# 1-Schematic.net
KiCad netlist of a schematic drawn in EasyEDA
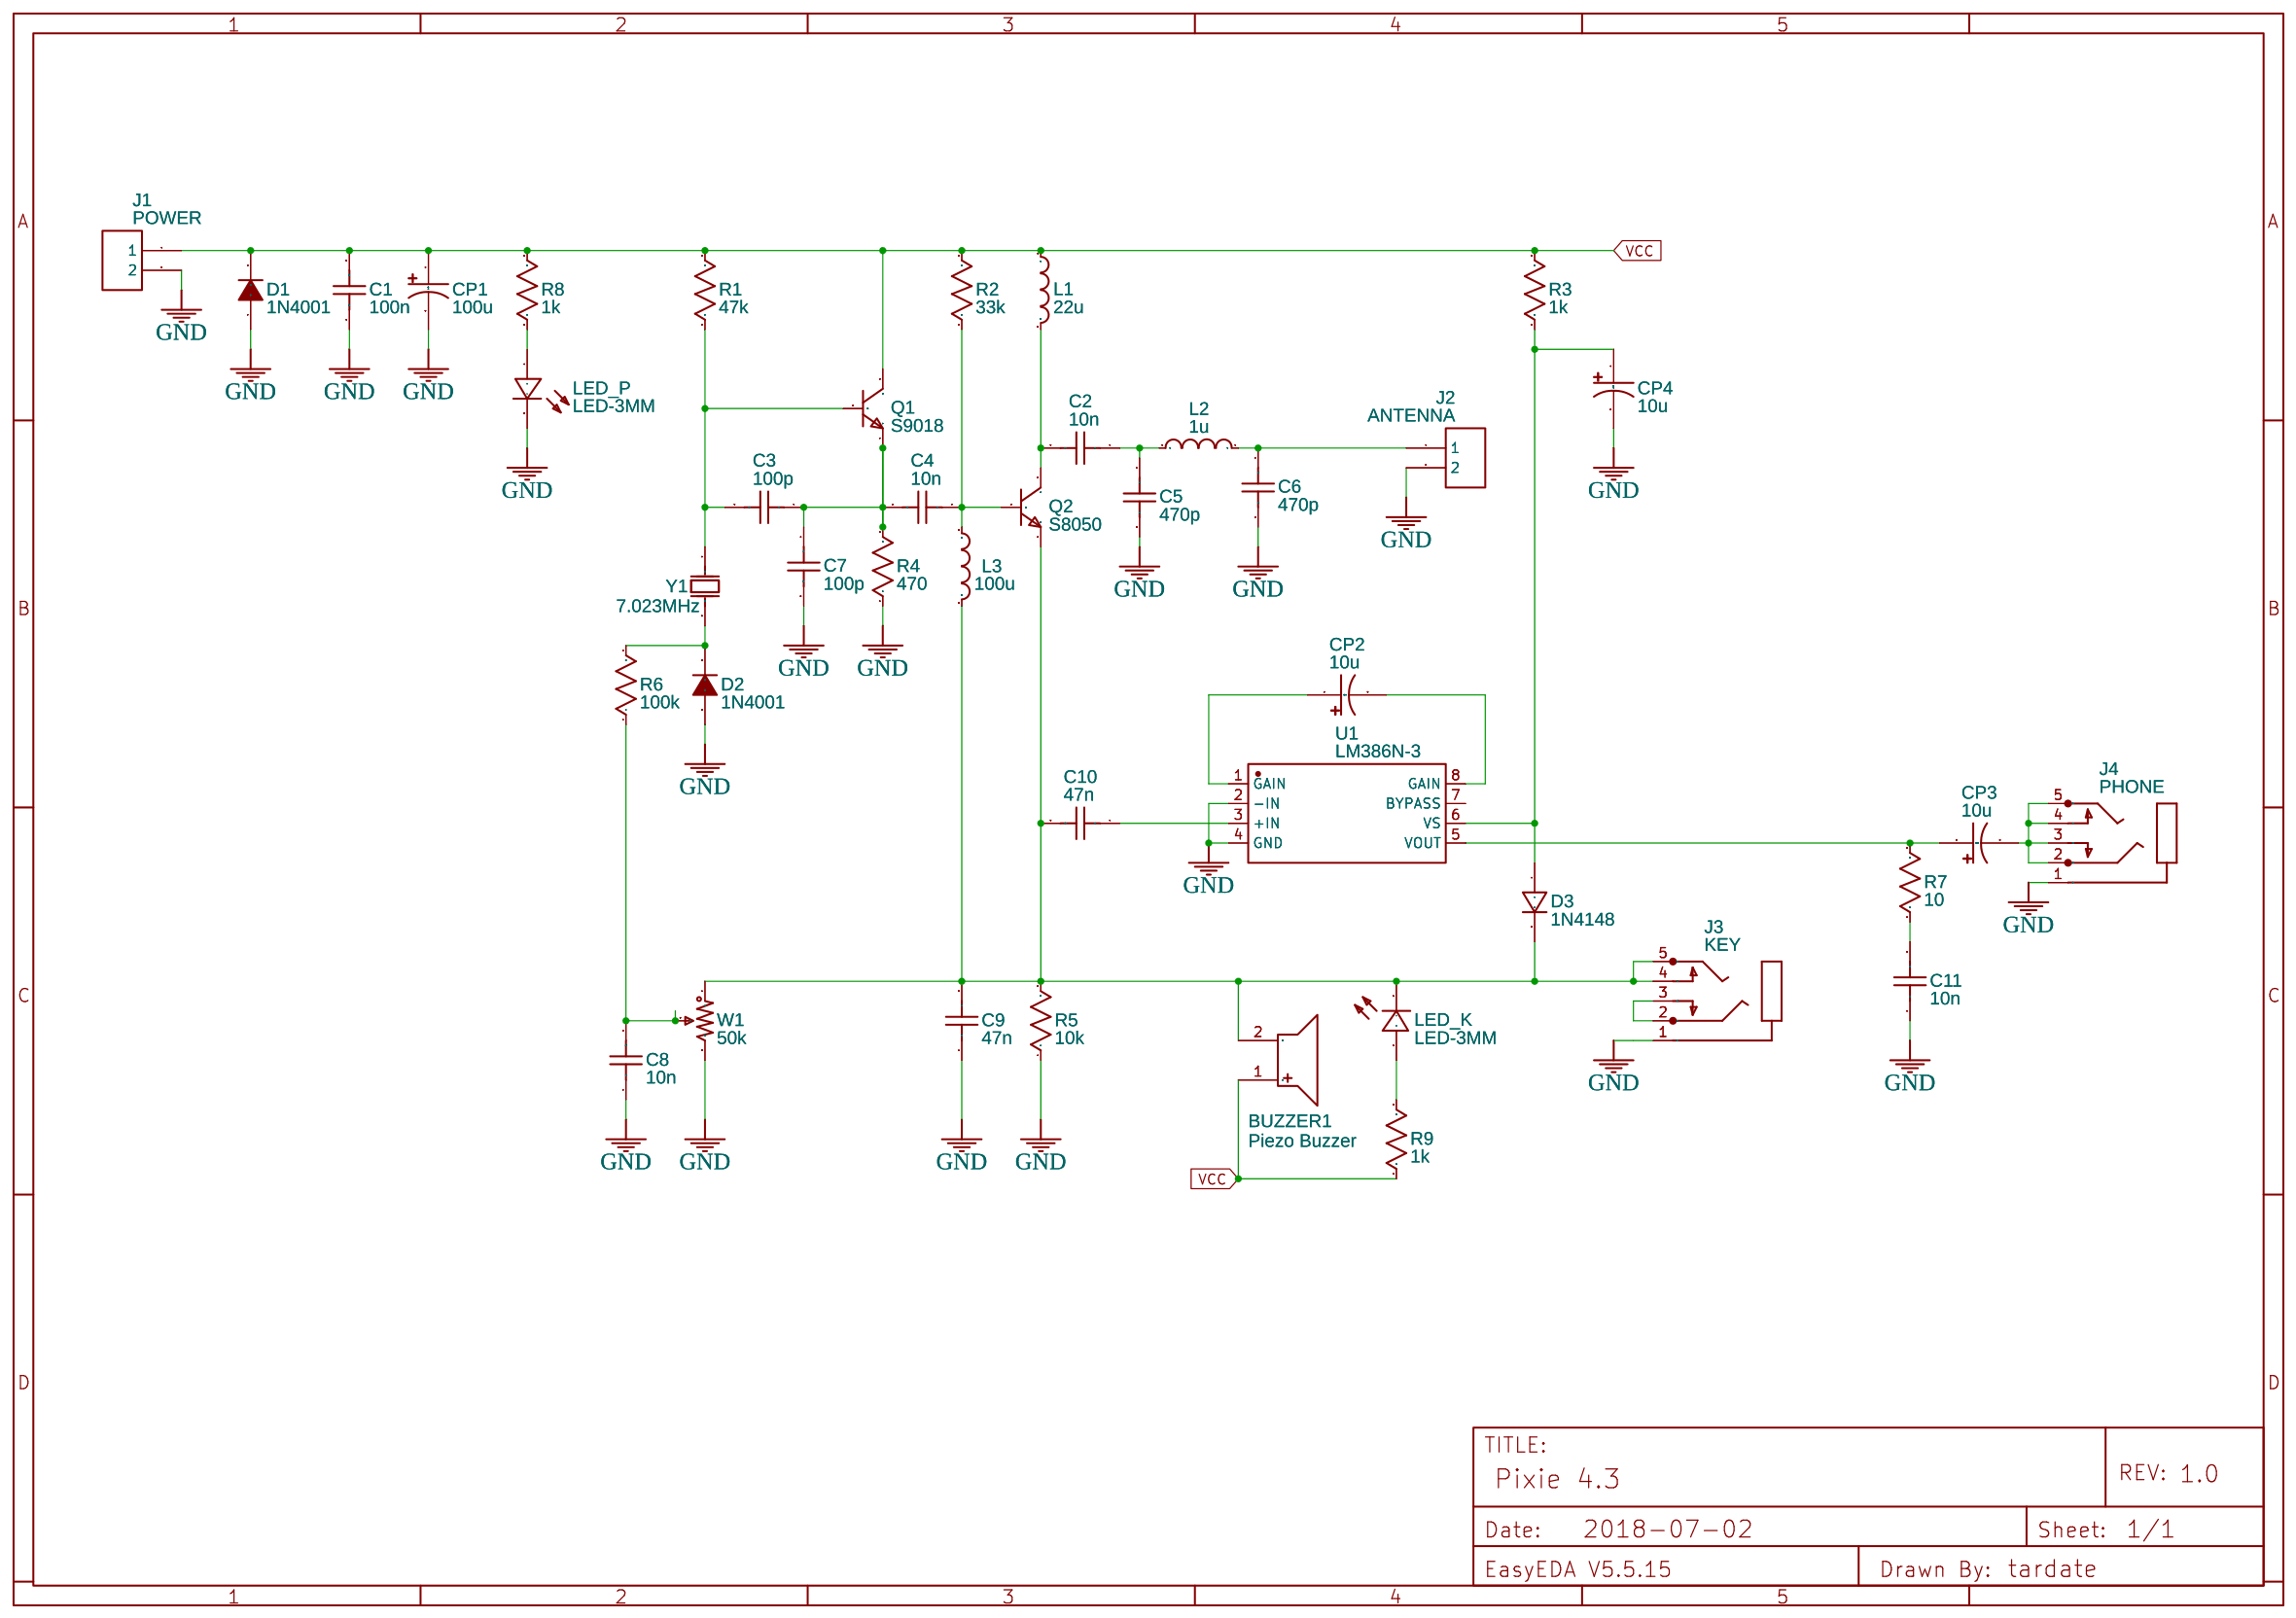
[diagram p0: schematic sheet]

(export (version "E")
  (design (tool "Eeschema 10.0.6"))
  (components
    (comp (ref "BUZZER1")
      (value "Piezo Buzzer")
      (fields (field (name "BOM_Manufacturer Part") "buzzerHMB1275-12B"))
      (libsource (lib "") (part "Unknown_640_530"))
    )
    (comp (ref "C1")
      (value "100n")
      (fields (field (name "BOM_Manufacturer Part") "?"))
      (libsource (lib "") (part "Cap_RAD-0.1_US"))
    )
    (comp (ref "C2")
      (value "10n")
      (fields (field (name "BOM_Manufacturer Part") "?"))
      (libsource (lib "") (part "Cap_RAD-0.1_US_2"))
    )
    (comp (ref "C3")
      (value "100p")
      (fields (field (name "BOM_Manufacturer Part") "?"))
      (libsource (lib "") (part "Cap_RAD-0.1_US_2"))
    )
    (comp (ref "C4")
      (value "10n")
      (fields (field (name "BOM_Manufacturer Part") "?"))
      (libsource (lib "") (part "Cap_RAD-0.1_US_2"))
    )
    (comp (ref "C5")
      (value "470p")
      (fields (field (name "BOM_Manufacturer Part") "?"))
      (libsource (lib "") (part "Cap_RAD-0.1_US_1"))
    )
    (comp (ref "C6")
      (value "470p")
      (fields (field (name "BOM_Manufacturer Part") "?"))
      (libsource (lib "") (part "Cap_RAD-0.1_US_1"))
    )
    (comp (ref "C7")
      (value "100p")
      (fields (field (name "BOM_Manufacturer Part") "?"))
      (libsource (lib "") (part "Cap_RAD-0.1_US_1"))
    )
    (comp (ref "C8")
      (value "10n")
      (fields (field (name "BOM_Manufacturer Part") "?"))
      (libsource (lib "") (part "Cap_RAD-0.1_US"))
    )
    (comp (ref "C9")
      (value "47n")
      (fields (field (name "BOM_Manufacturer Part") "?"))
      (libsource (lib "") (part "Cap_RAD-0.1_US"))
    )
    (comp (ref "C10")
      (value "47n")
      (fields (field (name "BOM_Manufacturer Part") "?"))
      (libsource (lib "") (part "Cap_RAD-0.1_US_2"))
    )
    (comp (ref "C11")
      (value "10n")
      (fields (field (name "BOM_Manufacturer Part") "?"))
      (libsource (lib "") (part "Cap_RAD-0.1_US"))
    )
    (comp (ref "CP1")
      (value "100u")
      (fields (field (name "BOM_Manufacturer Part") "?"))
      (libsource (lib "") (part "Cap_Electrolytic(TH)_D3.0XF1.5_US_2"))
    )
    (comp (ref "CP2")
      (value "10u")
      (fields (field (name "BOM_Manufacturer Part") "?"))
      (libsource (lib "") (part "Cap_Electrolytic(TH)_D3.0XF1.5_US"))
    )
    (comp (ref "CP3")
      (value "10u")
      (fields (field (name "BOM_Manufacturer Part") "?"))
      (libsource (lib "") (part "Cap_Electrolytic(TH)_D3.0XF1.5_US"))
    )
    (comp (ref "CP4")
      (value "10u")
      (fields (field (name "BOM_Manufacturer Part") "?"))
      (libsource (lib "") (part "Cap_Electrolytic(TH)_D3.0XF1.5_US_1"))
    )
    (comp (ref "D1")
      (value "1N4001")
      (fields (field (name "BOM_Manufacturer Part") "1N4001-E3/73"))
      (libsource (lib "") (part "Unknown_120_140"))
    )
    (comp (ref "D2")
      (value "1N4001")
      (fields (field (name "BOM_Manufacturer Part") "1N4001-E3/73"))
      (libsource (lib "") (part "Unknown_350_340"))
    )
    (comp (ref "D3")
      (value "1N4148")
      (fields (field (name "BOM_Manufacturer Part") "1N4448"))
      (libsource (lib "") (part "Unknown_770_450"))
    )
    (comp (ref "J1")
      (value "POWER")
      (fields (field (name "BOM_Manufacturer Part") "?"))
      (libsource (lib "") (part "Unknown_45_110"))
    )
    (comp (ref "J2")
      (value "ANTENNA")
      (fields (field (name "BOM_Manufacturer Part") "?"))
      (libsource (lib "") (part "Unknown_745_210"))
    )
    (comp (ref "J3")
      (value "KEY")
      (fields (field (name "BOM_Manufacturer Part") "?"))
      (libsource (lib "") (part "Unknown_880_490"))
    )
    (comp (ref "J4")
      (value "PHONE")
      (fields (field (name "BOM_Manufacturer Part") "?"))
      (libsource (lib "") (part "Unknown_1080_410"))
    )
    (comp (ref "L1")
      (value "22u")
      (fields (field (name "BOM_Manufacturer Part") "?"))
      (libsource (lib "") (part "Inductor_AXIAL-0.4_US_2"))
    )
    (comp (ref "L2")
      (value "1u")
      (fields (field (name "BOM_Manufacturer Part") "?"))
      (libsource (lib "") (part "Inductor_AXIAL-0.4_US_1"))
    )
    (comp (ref "L3")
      (value "100u")
      (fields (field (name "BOM_Manufacturer Part") "?"))
      (libsource (lib "") (part "Inductor_AXIAL-0.4_US"))
    )
    (comp (ref "LED_K")
      (value "LED-3MM")
      (fields (field (name "BOM_Manufacturer Part") "204-10SURD/S530-A3"))
      (libsource (lib "") (part "Unknown_700_510"))
    )
    (comp (ref "LED_P")
      (value "LED-3MM")
      (fields (field (name "BOM_Manufacturer Part") "204-10SURD/S530-A3"))
      (libsource (lib "") (part "Unknown_260_190"))
    )
    (comp (ref "Q1")
      (value "S9018")
      (fields (field (name "BOM_Manufacturer Part") "2N3904"))
      (libsource (lib "") (part "Unknown_430_200"))
    )
    (comp (ref "Q2")
      (value "S8050")
      (fields (field (name "BOM_Manufacturer Part") "2N3904"))
      (libsource (lib "") (part "Unknown_510_250"))
    )
    (comp (ref "R1")
      (value "47k")
      (fields (field (name "BOM_Manufacturer Part") "?"))
      (libsource (lib "") (part "Res_AXIAL-0.3(1/8W)_US"))
    )
    (comp (ref "R2")
      (value "33k")
      (fields (field (name "BOM_Manufacturer Part") "?"))
      (libsource (lib "") (part "Res_AXIAL-0.3(1/8W)_US"))
    )
    (comp (ref "R3")
      (value "1k")
      (fields (field (name "BOM_Manufacturer Part") "?"))
      (libsource (lib "") (part "Res_AXIAL-0.3(1/8W)_US"))
    )
    (comp (ref "R4")
      (value "470")
      (fields (field (name "BOM_Manufacturer Part") "?"))
      (libsource (lib "") (part "Res_AXIAL-0.3(1/8W)_US"))
    )
    (comp (ref "R5")
      (value "10k")
      (fields (field (name "BOM_Manufacturer Part") "?"))
      (libsource (lib "") (part "Res_AXIAL-0.3(1/8W)_US"))
    )
    (comp (ref "R6")
      (value "100k")
      (fields (field (name "BOM_Manufacturer Part") "?"))
      (libsource (lib "") (part "Res_AXIAL-0.3(1/8W)_US"))
    )
    (comp (ref "R7")
      (value "10")
      (fields (field (name "BOM_Manufacturer Part") "?"))
      (libsource (lib "") (part "Res_AXIAL-0.3(1/8W)_US"))
    )
    (comp (ref "R8")
      (value "1k")
      (fields (field (name "BOM_Manufacturer Part") "?"))
      (libsource (lib "") (part "Res_AXIAL-0.3(1/8W)_US"))
    )
    (comp (ref "R9")
      (value "1k")
      (fields (field (name "BOM_Manufacturer Part") "?"))
      (libsource (lib "") (part "Res_AXIAL-0.3(1/8W)_US"))
    )
    (comp (ref "U1") (value "LM386N-3") (libsource (lib "") (part "Unknown_665_410")))
    (comp (ref "W1")
      (value "50k")
      (fields (field (name "BOM_Manufacturer Part") "3386P-1-101LF"))
      (libsource (lib "") (part "3386P-1-101LF_US"))
    )
    (comp (ref "Y1")
      (value "7.023MHz")
      (fields (field (name "BOM_Manufacturer Part") "X49SD12MSD2SC"))
      (libsource (lib "") (part "X49SD12MSD2SC"))
    )
  )
  (nets
    (net (code "1") (name "GND") (class "Default")
      (node (ref "C1") (pin "1") (pinfunction "1_1") (pintype "unspecified"))
      (node (ref "C11") (pin "1") (pinfunction "1_1") (pintype "unspecified"))
      (node (ref "C5") (pin "2") (pinfunction "2_2") (pintype "unspecified"))
      (node (ref "C6") (pin "2") (pinfunction "2_2") (pintype "unspecified"))
      (node (ref "C7") (pin "2") (pinfunction "2_2") (pintype "unspecified"))
      (node (ref "C8") (pin "1") (pinfunction "1_1") (pintype "unspecified"))
      (node (ref "C9") (pin "1") (pinfunction "1_1") (pintype "unspecified"))
      (node (ref "CP1") (pin "2") (pinfunction "2_2") (pintype "unspecified"))
      (node (ref "CP4") (pin "2") (pinfunction "2_2") (pintype "unspecified"))
      (node (ref "D1") (pin "1") (pinfunction "A_1") (pintype "unspecified"))
      (node (ref "D2") (pin "1") (pinfunction "A_1") (pintype "unspecified"))
      (node (ref "J1") (pin "2") (pinfunction "2_2") (pintype "unspecified"))
      (node (ref "J2") (pin "2") (pinfunction "2_2") (pintype "unspecified"))
      (node (ref "J3") (pin "1") (pinfunction "1_1") (pintype "unspecified"))
      (node (ref "J4") (pin "1") (pinfunction "1_1") (pintype "unspecified"))
      (node (ref "LED_P") (pin "2") (pinfunction "-_2") (pintype "unspecified"))
      (node (ref "R4") (pin "1") (pinfunction "1_1") (pintype "unspecified"))
      (node (ref "R5") (pin "1") (pinfunction "1_1") (pintype "unspecified"))
      (node (ref "U1") (pin "2") (pinfunction "-IN_2") (pintype "unspecified"))
      (node (ref "U1") (pin "4") (pinfunction "GND_4") (pintype "unspecified"))
      (node (ref "W1") (pin "3") (pinfunction "3_3") (pintype "unspecified"))
    )
    (net (code "2") (name "Net-(C2-Pad1)") (class "Default")
      (node (ref "C2") (pin "1") (pinfunction "1_1") (pintype "unspecified"))
      (node (ref "C5") (pin "1") (pinfunction "1_1") (pintype "unspecified"))
      (node (ref "L2") (pin "1") (pinfunction "1_1") (pintype "unspecified"))
    )
    (net (code "3") (name "Net-(C6-Pad1)") (class "Default")
      (node (ref "C6") (pin "1") (pinfunction "1_1") (pintype "unspecified"))
      (node (ref "J2") (pin "1") (pinfunction "1_1") (pintype "unspecified"))
      (node (ref "L2") (pin "2") (pinfunction "2_2") (pintype "unspecified"))
    )
    (net (code "4") (name "Net-(C8-Pad2)") (class "Default")
      (node (ref "C8") (pin "2") (pinfunction "2_2") (pintype "unspecified"))
      (node (ref "R6") (pin "1") (pinfunction "1_1") (pintype "unspecified"))
      (node (ref "W1") (pin "2") (pinfunction "2_2") (pintype "unspecified"))
    )
    (net (code "5") (name "Net-(C11-Pad2)") (class "Default")
      (node (ref "C11") (pin "2") (pinfunction "2_2") (pintype "unspecified"))
      (node (ref "R7") (pin "1") (pinfunction "1_1") (pintype "unspecified"))
    )
    (net (code "6") (name "Net-(CP2-Pad1)") (class "Default")
      (node (ref "CP2") (pin "1") (pinfunction "1_1") (pintype "unspecified"))
      (node (ref "U1") (pin "1") (pinfunction "GAIN_1") (pintype "unspecified"))
    )
    (net (code "7") (name "Net-(CP2-Pad2)") (class "Default")
      (node (ref "CP2") (pin "2") (pinfunction "2_2") (pintype "unspecified"))
      (node (ref "U1") (pin "8") (pinfunction "GAIN_8") (pintype "unspecified"))
    )
    (net (code "8") (name "Net-(CP3-Pad2)") (class "Default")
      (node (ref "CP3") (pin "2") (pinfunction "2_2") (pintype "unspecified"))
      (node (ref "J4") (pin "2") (pinfunction "2_2") (pintype "unspecified"))
      (node (ref "J4") (pin "3") (pinfunction "3_3") (pintype "unspecified"))
      (node (ref "J4") (pin "4") (pinfunction "4_4") (pintype "unspecified"))
      (node (ref "J4") (pin "5") (pinfunction "5_5") (pintype "unspecified"))
    )
    (net (code "9") (name "Net-(D2-K)") (class "Default")
      (node (ref "D2") (pin "2") (pinfunction "K_2") (pintype "unspecified"))
      (node (ref "R6") (pin "2") (pinfunction "2_2") (pintype "unspecified"))
      (node (ref "Y1") (pin "2") (pinfunction "OSC2_2") (pintype "input"))
    )
    (net (code "10") (name "Net-(D3-A)") (class "Default")
      (node (ref "CP4") (pin "1") (pinfunction "1_1") (pintype "unspecified"))
      (node (ref "D3") (pin "1") (pinfunction "A_1") (pintype "unspecified"))
      (node (ref "R3") (pin "1") (pinfunction "1_1") (pintype "unspecified"))
      (node (ref "U1") (pin "6") (pinfunction "VS_6") (pintype "unspecified"))
    )
    (net (code "11") (name "Net-(D3-K)") (class "Default")
      (node (ref "BUZZER1") (pin "2") (pinfunction "2_2") (pintype "unspecified"))
      (node (ref "C10") (pin "2") (pinfunction "2_2") (pintype "unspecified"))
      (node (ref "C9") (pin "2") (pinfunction "2_2") (pintype "unspecified"))
      (node (ref "D3") (pin "2") (pinfunction "K_2") (pintype "unspecified"))
      (node (ref "J3") (pin "4") (pinfunction "4_4") (pintype "unspecified"))
      (node (ref "J3") (pin "5") (pinfunction "5_5") (pintype "unspecified"))
      (node (ref "L3") (pin "2") (pinfunction "2_2") (pintype "unspecified"))
      (node (ref "LED_K") (pin "2") (pinfunction "-_2") (pintype "unspecified"))
      (node (ref "Q2") (pin "1") (pinfunction "E_1") (pintype "unspecified"))
      (node (ref "R5") (pin "2") (pinfunction "2_2") (pintype "unspecified"))
      (node (ref "W1") (pin "1") (pinfunction "1_1") (pintype "unspecified"))
    )
    (net (code "12") (name "Net-(J3-Pad2)") (class "Default")
      (node (ref "J3") (pin "2") (pinfunction "2_2") (pintype "unspecified"))
      (node (ref "J3") (pin "3") (pinfunction "3_3") (pintype "unspecified"))
    )
    (net (code "13") (name "Net-(LED_K-+)") (class "Default")
      (node (ref "LED_K") (pin "1") (pinfunction "+_1") (pintype "unspecified"))
      (node (ref "R9") (pin "2") (pinfunction "2_2") (pintype "unspecified"))
    )
    (net (code "14") (name "Net-(LED_P-+)") (class "Default")
      (node (ref "LED_P") (pin "1") (pinfunction "+_1") (pintype "unspecified"))
      (node (ref "R8") (pin "1") (pinfunction "1_1") (pintype "unspecified"))
    )
    (net (code "15") (name "Net-(Q1-B)") (class "Default")
      (node (ref "C3") (pin "2") (pinfunction "2_2") (pintype "unspecified"))
      (node (ref "Q1") (pin "2") (pinfunction "B_2") (pintype "unspecified"))
      (node (ref "R1") (pin "1") (pinfunction "1_1") (pintype "unspecified"))
      (node (ref "Y1") (pin "1") (pinfunction "OSC1_1") (pintype "input"))
    )
    (net (code "16") (name "Net-(Q1-E)") (class "Default")
      (node (ref "C3") (pin "1") (pinfunction "1_1") (pintype "unspecified"))
      (node (ref "C4") (pin "2") (pinfunction "2_2") (pintype "unspecified"))
      (node (ref "C7") (pin "1") (pinfunction "1_1") (pintype "unspecified"))
      (node (ref "Q1") (pin "1") (pinfunction "E_1") (pintype "unspecified"))
      (node (ref "R4") (pin "2") (pinfunction "2_2") (pintype "unspecified"))
    )
    (net (code "17") (name "Net-(Q2-B)") (class "Default")
      (node (ref "C4") (pin "1") (pinfunction "1_1") (pintype "unspecified"))
      (node (ref "L3") (pin "1") (pinfunction "1_1") (pintype "unspecified"))
      (node (ref "Q2") (pin "2") (pinfunction "B_2") (pintype "unspecified"))
      (node (ref "R2") (pin "1") (pinfunction "1_1") (pintype "unspecified"))
    )
    (net (code "18") (name "Net-(Q2-C)") (class "Default")
      (node (ref "C2") (pin "2") (pinfunction "2_2") (pintype "unspecified"))
      (node (ref "L1") (pin "2") (pinfunction "2_2") (pintype "unspecified"))
      (node (ref "Q2") (pin "3") (pinfunction "C_3") (pintype "unspecified"))
    )
    (net (code "19") (name "Net-(U1-+IN)") (class "Default")
      (node (ref "C10") (pin "1") (pinfunction "1_1") (pintype "unspecified"))
      (node (ref "U1") (pin "3") (pinfunction "+IN_3") (pintype "unspecified"))
    )
    (net (code "20") (name "Net-(U1-VOUT)") (class "Default")
      (node (ref "CP3") (pin "1") (pinfunction "1_1") (pintype "unspecified"))
      (node (ref "R7") (pin "2") (pinfunction "2_2") (pintype "unspecified"))
      (node (ref "U1") (pin "5") (pinfunction "VOUT_5") (pintype "unspecified"))
    )
    (net (code "21") (name "VCC") (class "Default")
      (node (ref "BUZZER1") (pin "1") (pinfunction "1_1") (pintype "unspecified"))
      (node (ref "C1") (pin "2") (pinfunction "2_2") (pintype "unspecified"))
      (node (ref "CP1") (pin "1") (pinfunction "1_1") (pintype "unspecified"))
      (node (ref "D1") (pin "2") (pinfunction "K_2") (pintype "unspecified"))
      (node (ref "J1") (pin "1") (pinfunction "1_1") (pintype "unspecified"))
      (node (ref "L1") (pin "1") (pinfunction "1_1") (pintype "unspecified"))
      (node (ref "Q1") (pin "3") (pinfunction "C_3") (pintype "unspecified"))
      (node (ref "R1") (pin "2") (pinfunction "2_2") (pintype "unspecified"))
      (node (ref "R2") (pin "2") (pinfunction "2_2") (pintype "unspecified"))
      (node (ref "R3") (pin "2") (pinfunction "2_2") (pintype "unspecified"))
      (node (ref "R8") (pin "2") (pinfunction "2_2") (pintype "unspecified"))
      (node (ref "R9") (pin "1") (pinfunction "1_1") (pintype "unspecified"))
    )
    (net (code "22") (name "unconnected-(U1-BYPASS-Pad7)") (class "Default")
      (node (ref "U1") (pin "7") (pinfunction "BYPASS_7") (pintype "unspecified"))
    )
  )
)
